# F1-T12_heater.net
KiCad netlist of a schematic drawn in EAGLE
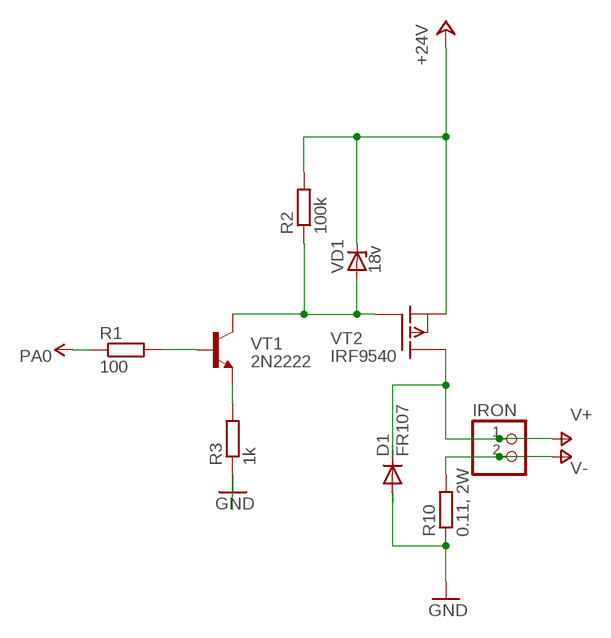
[diagram p0: schematic, sheet 1]

(export (version "E")
  (design (tool "Eeschema 10.0.6"))
  (components
    (comp (ref "D1")
      (value "FR107")
      (footprint "eagle-import:DO41-10")
      (libsource (lib "eagle-import") (part "1N4004"))
    )
    (comp (ref "IRON")
      (value "PINHD-1X2")
      (footprint "eagle-import:1X02")
      (libsource (lib "eagle-import") (part "PINHD-1X2"))
    )
    (comp (ref "R1")
      (value "100")
      (footprint "eagle-import:0204_5")
      (libsource (lib "eagle-import") (part "R-EU_0204/5"))
    )
    (comp (ref "R2")
      (value "100k")
      (footprint "eagle-import:0204_5")
      (libsource (lib "eagle-import") (part "R-EU_0204/5"))
    )
    (comp (ref "R3")
      (value "1k")
      (footprint "eagle-import:0204_5")
      (libsource (lib "eagle-import") (part "R-EU_0204/5"))
    )
    (comp (ref "R10")
      (value "0.11, 2W")
      (footprint "eagle-import:0204_5")
      (libsource (lib "eagle-import") (part "R-EU_0204/5"))
    )
    (comp (ref "VD1")
      (value "18v")
      (footprint "eagle-import:DO34Z7")
      (libsource (lib "eagle-import") (part "ZENER-DIODEDO34-7"))
    )
    (comp (ref "VT1")
      (value "2N2222")
      (footprint "eagle-import:TO18")
      (libsource (lib "eagle-import") (part "2N2222"))
    )
    (comp (ref "VT2")
      (value "IRF9540")
      (footprint "eagle-import:TO220")
      (libsource (lib "eagle-import") (part "IRF9530"))
    )
  )
  (nets
    (net (code "1") (name "+24V") (class "Default")
      (node (ref "R2") (pin "2") (pinfunction "2_2") (pintype "passive"))
      (node (ref "VD1") (pin "C") (pinfunction "C_C") (pintype "passive"))
      (node (ref "VT2") (pin "3") (pinfunction "S_3") (pintype "passive"))
    )
    (net (code "2") (name "GND") (class "Default")
      (node (ref "D1") (pin "A") (pinfunction "A_A") (pintype "passive"))
      (node (ref "R10") (pin "1") (pinfunction "1_1") (pintype "passive"))
      (node (ref "R3") (pin "1") (pinfunction "1_1") (pintype "passive"))
    )
    (net (code "3") (name "Net-(VT1-B)") (class "Default")
      (node (ref "R1") (pin "2") (pinfunction "2_2") (pintype "passive"))
      (node (ref "VT1") (pin "2") (pinfunction "B_2") (pintype "passive"))
    )
    (net (code "4") (name "Net-(VT1-C)") (class "Default")
      (node (ref "R2") (pin "1") (pinfunction "1_1") (pintype "passive"))
      (node (ref "VD1") (pin "A") (pinfunction "A_A") (pintype "passive"))
      (node (ref "VT1") (pin "3") (pinfunction "C_3") (pintype "passive"))
      (node (ref "VT2") (pin "1") (pinfunction "G_1") (pintype "passive"))
    )
    (net (code "5") (name "Net-(VT1-E)") (class "Default")
      (node (ref "R3") (pin "2") (pinfunction "2_2") (pintype "passive"))
      (node (ref "VT1") (pin "1") (pinfunction "E_1") (pintype "passive"))
    )
    (net (code "6") (name "PA0") (class "Default")
      (node (ref "R1") (pin "1") (pinfunction "1_1") (pintype "passive"))
    )
    (net (code "7") (name "V+") (class "Default")
      (node (ref "D1") (pin "C") (pinfunction "C_C") (pintype "passive"))
      (node (ref "IRON") (pin "1") (pinfunction "1_1") (pintype "passive"))
      (node (ref "VT2") (pin "2") (pinfunction "D_2") (pintype "passive"))
    )
    (net (code "8") (name "V-") (class "Default")
      (node (ref "IRON") (pin "2") (pinfunction "2_2") (pintype "passive"))
      (node (ref "R10") (pin "2") (pinfunction "2_2") (pintype "passive"))
    )
  )
)
